# K-Diag_small-_double.net
KiCad netlist of a schematic drawn in EAGLE
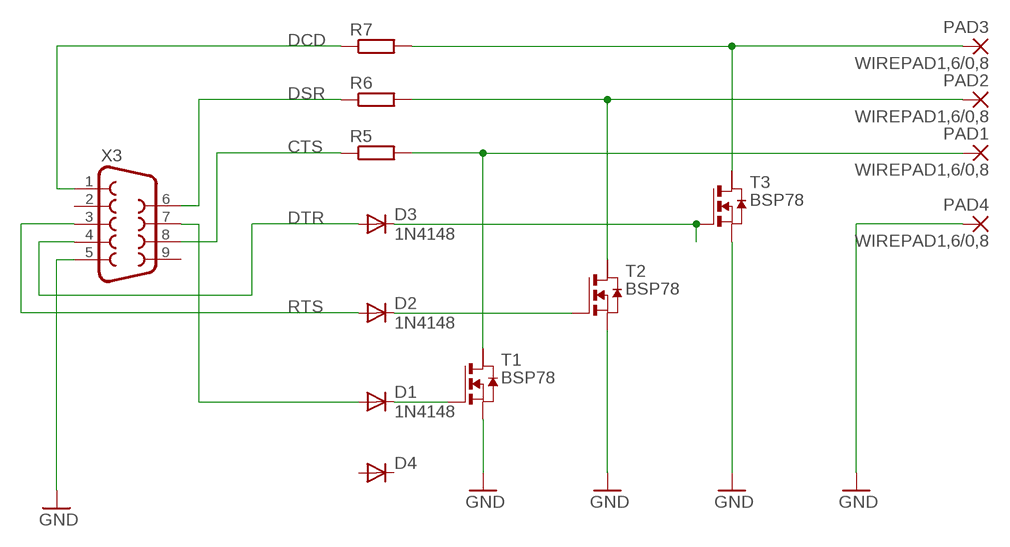
[diagram p0: schematic, sheet 1]

(export (version "E")
  (design (tool "Eeschema 10.0.6"))
  (components
    (comp (ref "D1")
      (value "1N4148")
      (footprint "eagle-import:SOD323-W")
      (libsource (lib "eagle-import") (part "DIODE-SOD323-W"))
    )
    (comp (ref "D2")
      (value "1N4148")
      (footprint "eagle-import:SOD323-W")
      (libsource (lib "eagle-import") (part "DIODE-SOD323-W"))
    )
    (comp (ref "D3")
      (value "1N4148")
      (footprint "eagle-import:SOD323-W")
      (libsource (lib "eagle-import") (part "DIODE-SOD323-W"))
    )
    (comp (ref "D4")
      (value "DIODE-SOD323-W")
      (footprint "eagle-import:SOD323-W")
      (libsource (lib "eagle-import") (part "DIODE-SOD323-W"))
    )
    (comp (ref "PAD1")
      (value "WIREPAD1,6/0,8")
      (footprint "eagle-import:1,6_0,8")
      (libsource (lib "eagle-import") (part "WIREPAD1,6/0,8"))
    )
    (comp (ref "PAD2")
      (value "WIREPAD1,6/0,8")
      (footprint "eagle-import:1,6_0,8")
      (libsource (lib "eagle-import") (part "WIREPAD1,6/0,8"))
    )
    (comp (ref "PAD3")
      (value "WIREPAD1,6/0,8")
      (footprint "eagle-import:1,6_0,8")
      (libsource (lib "eagle-import") (part "WIREPAD1,6/0,8"))
    )
    (comp (ref "PAD4")
      (value "WIREPAD1,6/0,8")
      (footprint "eagle-import:1,6_0,8")
      (libsource (lib "eagle-import") (part "WIREPAD1,6/0,8"))
    )
    (comp (ref "R5")
      (value "R-EU_R0805")
      (footprint "eagle-import:R0805")
      (libsource (lib "eagle-import") (part "R-EU_R0805"))
    )
    (comp (ref "R6")
      (value "R-EU_R0805")
      (footprint "eagle-import:R0805")
      (libsource (lib "eagle-import") (part "R-EU_R0805"))
    )
    (comp (ref "R7")
      (value "R-EU_R0805")
      (footprint "eagle-import:R0805")
      (libsource (lib "eagle-import") (part "R-EU_R0805"))
    )
    (comp (ref "T1")
      (value "BSP78")
      (footprint "eagle-import:SOT223")
      (libsource (lib "eagle-import") (part "NMOSSOT223"))
    )
    (comp (ref "T2")
      (value "BSP78")
      (footprint "eagle-import:SOT223")
      (libsource (lib "eagle-import") (part "NMOSSOT223"))
    )
    (comp (ref "T3")
      (value "BSP78")
      (footprint "eagle-import:SOT223")
      (libsource (lib "eagle-import") (part "NMOSSOT223"))
    )
    (comp (ref "X3")
      (value "F09D")
      (footprint "eagle-import:F09D")
      (libsource (lib "eagle-import") (part "F09D"))
    )
  )
  (nets
    (net (code "1") (name "/CTS") (class "Default")
      (node (ref "R5") (pin "1") (pinfunction "1_1") (pintype "passive"))
      (node (ref "X3") (pin "8") (pinfunction "8_8") (pintype "passive"))
    )
    (net (code "2") (name "/DCD") (class "Default")
      (node (ref "R7") (pin "1") (pinfunction "1_1") (pintype "passive"))
      (node (ref "X3") (pin "1") (pinfunction "1_1") (pintype "passive"))
    )
    (net (code "3") (name "/DSR") (class "Default")
      (node (ref "R6") (pin "1") (pinfunction "1_1") (pintype "passive"))
      (node (ref "X3") (pin "6") (pinfunction "6_6") (pintype "passive"))
    )
    (net (code "4") (name "/DTR") (class "Default")
      (node (ref "D3") (pin "A") (pinfunction "A_A") (pintype "passive"))
      (node (ref "X3") (pin "4") (pinfunction "4_4") (pintype "passive"))
    )
    (net (code "5") (name "/RTS") (class "Default")
      (node (ref "D2") (pin "A") (pinfunction "A_A") (pintype "passive"))
      (node (ref "X3") (pin "3") (pinfunction "3_3") (pintype "passive"))
    )
    (net (code "6") (name "GND") (class "Default")
      (node (ref "PAD4") (pin "1") (pinfunction "P_1") (pintype "passive"))
      (node (ref "T1") (pin "3") (pinfunction "S_3") (pintype "passive"))
      (node (ref "T2") (pin "3") (pinfunction "S_3") (pintype "passive"))
      (node (ref "T3") (pin "3") (pinfunction "S_3") (pintype "passive"))
      (node (ref "X3") (pin "5") (pinfunction "5_5") (pintype "passive"))
    )
    (net (code "7") (name "Net-(D1-PadA)") (class "Default")
      (node (ref "D1") (pin "A") (pinfunction "A_A") (pintype "passive"))
      (node (ref "X3") (pin "7") (pinfunction "7_7") (pintype "passive"))
    )
    (net (code "8") (name "Net-(PAD1-P)") (class "Default")
      (node (ref "PAD1") (pin "1") (pinfunction "P_1") (pintype "passive"))
      (node (ref "R5") (pin "2") (pinfunction "2_2") (pintype "passive"))
      (node (ref "T1") (pin "2") (pinfunction "D_2") (pintype "passive"))
    )
    (net (code "9") (name "Net-(PAD2-P)") (class "Default")
      (node (ref "PAD2") (pin "1") (pinfunction "P_1") (pintype "passive"))
      (node (ref "R6") (pin "2") (pinfunction "2_2") (pintype "passive"))
      (node (ref "T2") (pin "2") (pinfunction "D_2") (pintype "passive"))
    )
    (net (code "10") (name "Net-(PAD3-P)") (class "Default")
      (node (ref "PAD3") (pin "1") (pinfunction "P_1") (pintype "passive"))
      (node (ref "R7") (pin "2") (pinfunction "2_2") (pintype "passive"))
      (node (ref "T3") (pin "2") (pinfunction "D_2") (pintype "passive"))
    )
    (net (code "11") (name "Net-(T1-G)") (class "Default")
      (node (ref "D1") (pin "C") (pinfunction "C_C") (pintype "passive"))
      (node (ref "T1") (pin "1") (pinfunction "G_1") (pintype "passive"))
    )
    (net (code "12") (name "Net-(T2-G)") (class "Default")
      (node (ref "D2") (pin "C") (pinfunction "C_C") (pintype "passive"))
      (node (ref "T2") (pin "1") (pinfunction "G_1") (pintype "passive"))
    )
    (net (code "13") (name "Net-(T3-G)") (class "Default")
      (node (ref "D3") (pin "C") (pinfunction "C_C") (pintype "passive"))
      (node (ref "T3") (pin "1") (pinfunction "G_1") (pintype "passive"))
    )
    (net (code "14") (name "unconnected-(D4-PadA)") (class "Default")
      (node (ref "D4") (pin "A") (pinfunction "A_A") (pintype "passive"))
    )
    (net (code "15") (name "unconnected-(D4-PadC)") (class "Default")
      (node (ref "D4") (pin "C") (pinfunction "C_C") (pintype "passive"))
    )
    (net (code "16") (name "unconnected-(T1-D2-Pad4)") (class "Default")
      (node (ref "T1") (pin "4") (pinfunction "D2_4") (pintype "passive"))
    )
    (net (code "17") (name "unconnected-(T2-D2-Pad4)") (class "Default")
      (node (ref "T2") (pin "4") (pinfunction "D2_4") (pintype "passive"))
    )
    (net (code "18") (name "unconnected-(T3-D2-Pad4)") (class "Default")
      (node (ref "T3") (pin "4") (pinfunction "D2_4") (pintype "passive"))
    )
    (net (code "19") (name "unconnected-(X3-Pad2)") (class "Default")
      (node (ref "X3") (pin "2") (pinfunction "2_2") (pintype "passive"))
    )
    (net (code "20") (name "unconnected-(X3-Pad9)") (class "Default")
      (node (ref "X3") (pin "9") (pinfunction "9_9") (pintype "passive"))
    )
  )
)
